# microbean.net
KiCad netlist of a schematic drawn in EAGLE
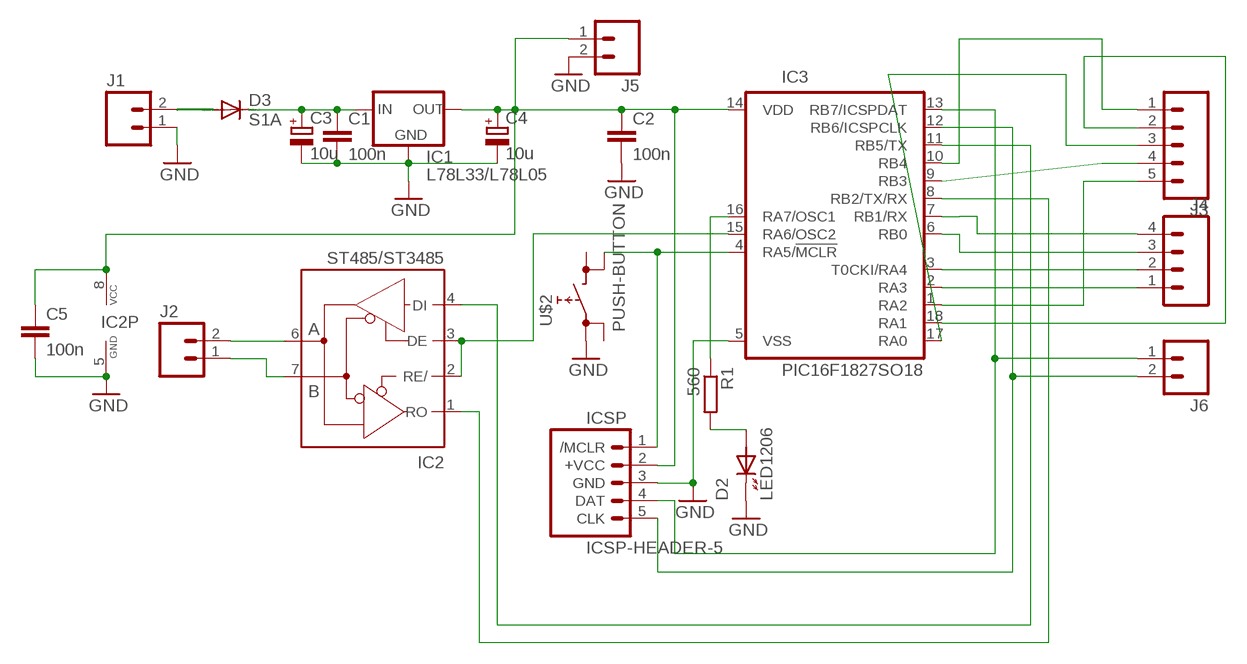
[diagram p0: schematic, sheet 1]

(export (version "E")
  (design (tool "Eeschema 10.0.6"))
  (components
    (comp (ref "C1")
      (value "100n")
      (footprint "eagle-import:C0805")
      (libsource (lib "eagle-import") (part "C-EUC0805"))
    )
    (comp (ref "C2")
      (value "100n")
      (footprint "eagle-import:C0805")
      (libsource (lib "eagle-import") (part "C-EUC0805"))
    )
    (comp (ref "C3")
      (value "10u")
      (footprint "eagle-import:UD-4X5,8_NICHICON")
      (libsource (lib "eagle-import") (part "CPOL-EUSMD4X5.3"))
    )
    (comp (ref "C4")
      (value "10u")
      (footprint "eagle-import:UD-4X5,8_NICHICON")
      (libsource (lib "eagle-import") (part "CPOL-EUSMD4X5.3"))
    )
    (comp (ref "C5")
      (value "100n")
      (footprint "eagle-import:C0805")
      (libsource (lib "eagle-import") (part "C-EUC0805"))
    )
    (comp (ref "D2")
      (value "LED1206")
      (footprint "eagle-import:CHIPLED_1206")
      (libsource (lib "eagle-import") (part "LED1206"))
    )
    (comp (ref "D3")
      (value "S1A")
      (footprint "eagle-import:SMA")
      (libsource (lib "eagle-import") (part "S1M"))
    )
    (comp (ref "IC1")
      (value "L78L33/L78L05")
      (footprint "eagle-import:SOT89")
      (libsource (lib "eagle-import") (part "78LXXSOT89"))
    )
    (comp (ref "IC2")
      (value "ST485/ST3485")
      (footprint "eagle-import:SO08")
      (libsource (lib "eagle-import") (part "MAX485ST3485"))
    )
    (comp (ref "IC3")
      (value "PIC16F1827SO18")
      (footprint "eagle-import:SO18W")
      (libsource (lib "eagle-import") (part "PIC16F1827SO18"))
    )
    (comp (ref "ICSP")
      (value "ICSP-HEADER-5")
      (footprint "eagle-import:1X05")
      (libsource (lib "eagle-import") (part "ICSP-HEADER-5"))
    )
    (comp (ref "J1")
      (value "M02-SCREW-3.5MM3.5MM")
      (footprint "eagle-import:SCREWTERMINAL-3.5MM-2")
      (libsource (lib "eagle-import") (part "M02-SCREW-3.5MM3.5MM"))
    )
    (comp (ref "J2")
      (value "M02-SCREW-3.5MM3.5MM")
      (footprint "eagle-import:SCREWTERMINAL-3.5MM-2")
      (libsource (lib "eagle-import") (part "M02-SCREW-3.5MM3.5MM"))
    )
    (comp (ref "J3")
      (value "M05PTH")
      (footprint "eagle-import:1X05")
      (libsource (lib "eagle-import") (part "M05PTH"))
    )
    (comp (ref "J4")
      (value "M04")
      (footprint "eagle-import:1X04")
      (libsource (lib "eagle-import") (part "M04"))
    )
    (comp (ref "J5")
      (value "M02")
      (footprint "eagle-import:1X02")
      (libsource (lib "eagle-import") (part "M02"))
    )
    (comp (ref "J6")
      (value "M02")
      (footprint "eagle-import:1X02")
      (libsource (lib "eagle-import") (part "M02"))
    )
    (comp (ref "R1")
      (value "560")
      (footprint "eagle-import:R0805")
      (libsource (lib "eagle-import") (part "R-EU_R0805"))
    )
    (comp (ref "U$2")
      (value "PUSH-BUTTON")
      (footprint "eagle-import:MICRO-SWITCH")
      (libsource (lib "eagle-import") (part "PUSH-BUTTON"))
    )
  )
  (nets
    (net (code "1") (name "GND") (class "Default")
      (node (ref "C1") (pin "2") (pinfunction "2_2") (pintype "passive"))
      (node (ref "C2") (pin "2") (pinfunction "2_2") (pintype "passive"))
      (node (ref "C3") (pin "-") (pinfunction "-_-") (pintype "passive"))
      (node (ref "C4") (pin "-") (pinfunction "-_-") (pintype "passive"))
      (node (ref "C5") (pin "2") (pinfunction "2_2") (pintype "passive"))
      (node (ref "D2") (pin "C") (pinfunction "K_C") (pintype "passive"))
      (node (ref "IC1") (pin "2") (pinfunction "GND_2") (pintype "input"))
      (node (ref "IC1") (pin "2@1") (pinfunction "GND_2@1") (pintype "input"))
      (node (ref "IC2") (pin "5") (pinfunction "GND_5") (pintype "power_in"))
      (node (ref "IC3") (pin "5") (pinfunction "VSS_5") (pintype "power_in"))
      (node (ref "ICSP") (pin "3") (pinfunction "GND_3") (pintype "passive"))
      (node (ref "J1") (pin "1") (pinfunction "1_1") (pintype "passive"))
      (node (ref "J5") (pin "2") (pinfunction "2_2") (pintype "passive"))
      (node (ref "U$2") (pin "1") (pinfunction "0_1") (pintype "passive"))
    )
    (net (code "2") (name "Net-(D2-PadA)") (class "Default")
      (node (ref "D2") (pin "A") (pinfunction "A_A") (pintype "passive"))
      (node (ref "R1") (pin "2") (pinfunction "2_2") (pintype "passive"))
    )
    (net (code "3") (name "Net-(D3-PadA)") (class "Default")
      (node (ref "D3") (pin "A") (pinfunction "A_A") (pintype "passive"))
      (node (ref "J1") (pin "2") (pinfunction "2_2") (pintype "passive"))
    )
    (net (code "4") (name "Net-(IC1-IN)") (class "Default")
      (node (ref "C1") (pin "1") (pinfunction "1_1") (pintype "passive"))
      (node (ref "C3") (pin "+") (pinfunction "+_+") (pintype "passive"))
      (node (ref "D3") (pin "C") (pinfunction "C_C") (pintype "passive"))
      (node (ref "IC1") (pin "3") (pinfunction "IN_3") (pintype "input"))
    )
    (net (code "5") (name "Net-(IC1-OUT)") (class "Default")
      (node (ref "C2") (pin "1") (pinfunction "1_1") (pintype "passive"))
      (node (ref "C4") (pin "+") (pinfunction "+_+") (pintype "passive"))
      (node (ref "C5") (pin "1") (pinfunction "1_1") (pintype "passive"))
      (node (ref "IC1") (pin "1") (pinfunction "OUT_1") (pintype "passive"))
      (node (ref "IC2") (pin "8") (pinfunction "VCC_8") (pintype "power_in"))
      (node (ref "IC3") (pin "14") (pinfunction "VDD_14") (pintype "power_in"))
      (node (ref "ICSP") (pin "2") (pinfunction "+VCC_2") (pintype "passive"))
      (node (ref "J5") (pin "1") (pinfunction "1_1") (pintype "passive"))
    )
    (net (code "6") (name "Net-(IC2A-A)") (class "Default")
      (node (ref "IC2") (pin "6") (pinfunction "A_6") (pintype "passive"))
      (node (ref "J2") (pin "2") (pinfunction "2_2") (pintype "passive"))
    )
    (net (code "7") (name "Net-(IC2A-B)") (class "Default")
      (node (ref "IC2") (pin "7") (pinfunction "B_7") (pintype "passive"))
      (node (ref "J2") (pin "1") (pinfunction "1_1") (pintype "passive"))
    )
    (net (code "8") (name "Net-(IC2A-DE)") (class "Default")
      (node (ref "IC2") (pin "2") (pinfunction "RE/_2") (pintype "input"))
      (node (ref "IC2") (pin "3") (pinfunction "DE_3") (pintype "input"))
      (node (ref "IC3") (pin "15") (pinfunction "RA6/OSC2_15") (pintype "output"))
    )
    (net (code "9") (name "Net-(IC2A-DI)") (class "Default")
      (node (ref "IC2") (pin "4") (pinfunction "DI_4") (pintype "input"))
      (node (ref "IC3") (pin "11") (pinfunction "RB5/TX_11") (pintype "bidirectional"))
    )
    (net (code "10") (name "Net-(IC2A-RO)") (class "Default")
      (node (ref "IC2") (pin "1") (pinfunction "RO_1") (pintype "output"))
      (node (ref "IC3") (pin "8") (pinfunction "RB2/TX/RX_8") (pintype "bidirectional"))
    )
    (net (code "11") (name "Net-(IC3-RA0)") (class "Default")
      (node (ref "IC3") (pin "17") (pinfunction "RA0_17") (pintype "bidirectional"))
      (node (ref "J3") (pin "3") (pinfunction "3_3") (pintype "passive"))
    )
    (net (code "12") (name "Net-(IC3-RA1)") (class "Default")
      (node (ref "IC3") (pin "18") (pinfunction "RA1_18") (pintype "bidirectional"))
      (node (ref "J3") (pin "2") (pinfunction "2_2") (pintype "passive"))
    )
    (net (code "13") (name "Net-(IC3-RA2)") (class "Default")
      (node (ref "IC3") (pin "1") (pinfunction "RA2_1") (pintype "bidirectional"))
      (node (ref "J3") (pin "5") (pinfunction "5_5") (pintype "passive"))
    )
    (net (code "14") (name "Net-(IC3-RA3)") (class "Default")
      (node (ref "IC3") (pin "2") (pinfunction "RA3_2") (pintype "bidirectional"))
      (node (ref "J4") (pin "1") (pinfunction "1_1") (pintype "passive"))
    )
    (net (code "15") (name "Net-(IC3-RA5{slash}~{MCLR})") (class "Default")
      (node (ref "IC3") (pin "4") (pinfunction "RA5/~{MCLR}_4") (pintype "input"))
      (node (ref "ICSP") (pin "1") (pinfunction "/MCLR_1") (pintype "passive"))
      (node (ref "U$2") (pin "4") (pinfunction "1_4") (pintype "passive"))
    )
    (net (code "16") (name "Net-(IC3-RA7{slash}OSC1)") (class "Default")
      (node (ref "IC3") (pin "16") (pinfunction "RA7/OSC1_16") (pintype "input"))
      (node (ref "R1") (pin "1") (pinfunction "1_1") (pintype "passive"))
    )
    (net (code "17") (name "Net-(IC3-RB0)") (class "Default")
      (node (ref "IC3") (pin "6") (pinfunction "RB0_6") (pintype "bidirectional"))
      (node (ref "J4") (pin "3") (pinfunction "3_3") (pintype "passive"))
    )
    (net (code "18") (name "Net-(IC3-RB1{slash}RX)") (class "Default")
      (node (ref "IC3") (pin "7") (pinfunction "RB1/RX_7") (pintype "bidirectional"))
      (node (ref "J4") (pin "4") (pinfunction "4_4") (pintype "passive"))
    )
    (net (code "19") (name "Net-(IC3-RB3)") (class "Default")
      (node (ref "IC3") (pin "9") (pinfunction "RB3_9") (pintype "bidirectional"))
      (node (ref "J3") (pin "4") (pinfunction "4_4") (pintype "passive"))
    )
    (net (code "20") (name "Net-(IC3-RB4)") (class "Default")
      (node (ref "IC3") (pin "10") (pinfunction "RB4_10") (pintype "bidirectional"))
      (node (ref "J3") (pin "1") (pinfunction "1_1") (pintype "passive"))
    )
    (net (code "21") (name "Net-(IC3-RB6{slash}ICSPCLK)") (class "Default")
      (node (ref "IC3") (pin "12") (pinfunction "RB6/ICSPCLK_12") (pintype "bidirectional"))
      (node (ref "ICSP") (pin "5") (pinfunction "CLK_5") (pintype "passive"))
      (node (ref "J6") (pin "2") (pinfunction "2_2") (pintype "passive"))
    )
    (net (code "22") (name "Net-(IC3-RB7{slash}ICSPDAT)") (class "Default")
      (node (ref "IC3") (pin "13") (pinfunction "RB7/ICSPDAT_13") (pintype "bidirectional"))
      (node (ref "ICSP") (pin "4") (pinfunction "DAT_4") (pintype "passive"))
      (node (ref "J6") (pin "1") (pinfunction "1_1") (pintype "passive"))
    )
    (net (code "23") (name "Net-(IC3-T0CKI{slash}RA4)") (class "Default")
      (node (ref "IC3") (pin "3") (pinfunction "T0CKI/RA4_3") (pintype "bidirectional"))
      (node (ref "J4") (pin "2") (pinfunction "2_2") (pintype "passive"))
    )
    (net (code "24") (name "unconnected-(U$2-0-Pad2)") (class "Default")
      (node (ref "U$2") (pin "2") (pinfunction "0_2") (pintype "passive"))
    )
    (net (code "25") (name "unconnected-(U$2-1-Pad3)") (class "Default")
      (node (ref "U$2") (pin "3") (pinfunction "1_3") (pintype "passive"))
    )
  )
)
